# PCB_LED_CALENDAR__ESP-12E.net
KiCad netlist of a schematic drawn in Altium Designer
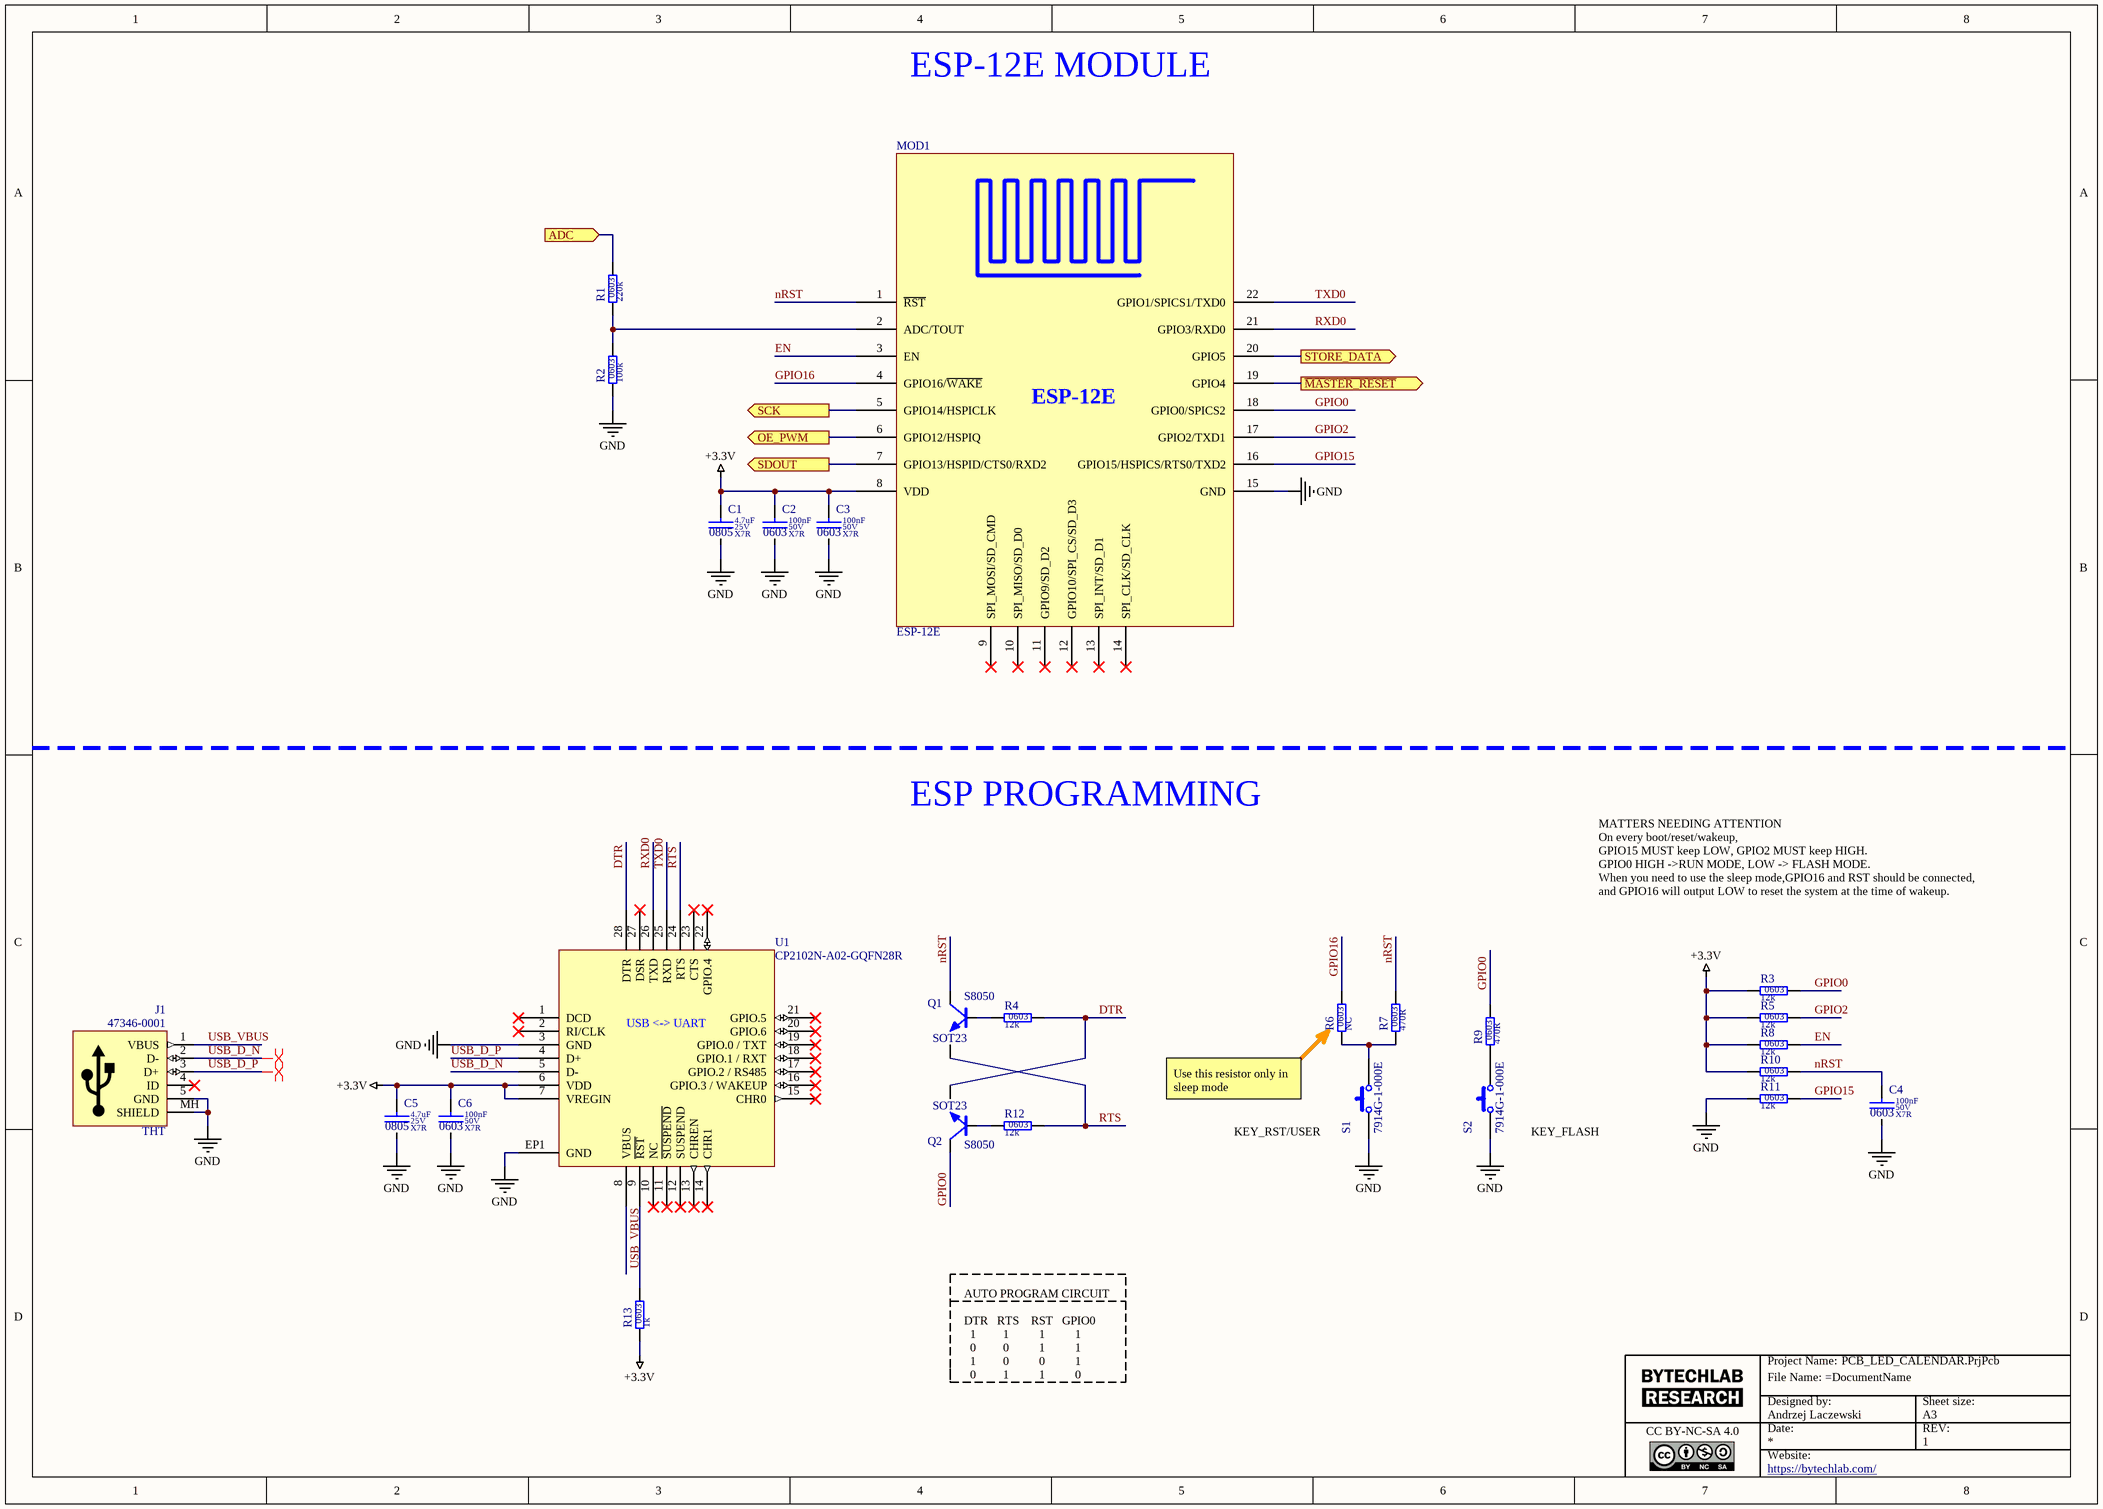
[diagram p0: PCB_LED_CALENDAR__ESP-12E.SchDoc]

(export (version "E")
  (design (tool "Eeschema 10.0.6"))
  (components
    (comp (ref "C1")
      (value "4.7uF")
      (footprint "C_0805_2012")
      (description "Capacitor")
      (fields
        (field (name "DIELECTRIC") "X7R")
        (field (name "VOLTAGE") "25V")
        (field (name "SCH_FOOTPRINT") "0805")
        (field (name "PART NUMBER") "C_4.7uF_25V_X7R_0805_10")
        (field (name "MANUFACTURER") "TDK")
      )
      (libsource (lib "Library") (part "C"))
    )
    (comp (ref "C2")
      (value "100nF")
      (footprint "C_0603_1608")
      (description "Capacitor")
      (fields
        (field (name "DIELECTRIC") "X7R")
        (field (name "VOLTAGE") "50V")
        (field (name "SCH_FOOTPRINT") "0603")
        (field (name "PART NUMBER") "C_100nF_50V_X7R_0603_5")
        (field (name "MANUFACTURER") "Samsung")
      )
      (libsource (lib "Library") (part "C"))
    )
    (comp (ref "C3")
      (value "100nF")
      (footprint "C_0603_1608")
      (description "Capacitor")
      (fields
        (field (name "DIELECTRIC") "X7R")
        (field (name "VOLTAGE") "50V")
        (field (name "SCH_FOOTPRINT") "0603")
        (field (name "PART NUMBER") "C_100nF_50V_X7R_0603_5")
        (field (name "MANUFACTURER") "Samsung")
      )
      (libsource (lib "Library") (part "C"))
    )
    (comp (ref "C4")
      (value "100nF")
      (footprint "C_0603_1608")
      (description "Capacitor")
      (fields
        (field (name "DIELECTRIC") "X7R")
        (field (name "VOLTAGE") "50V")
        (field (name "SCH_FOOTPRINT") "0603")
        (field (name "PART NUMBER") "C_100nF_50V_X7R_0603_5")
        (field (name "MANUFACTURER") "Samsung")
      )
      (libsource (lib "Library") (part "C"))
    )
    (comp (ref "C5")
      (value "4.7uF")
      (footprint "C_0805_2012")
      (description "Capacitor")
      (fields
        (field (name "DIELECTRIC") "X7R")
        (field (name "VOLTAGE") "25V")
        (field (name "SCH_FOOTPRINT") "0805")
        (field (name "PART NUMBER") "C_4.7uF_25V_X7R_0805_10")
        (field (name "MANUFACTURER") "TDK")
      )
      (libsource (lib "Library") (part "C"))
    )
    (comp (ref "C6")
      (value "100nF")
      (footprint "C_0603_1608")
      (description "Capacitor")
      (fields
        (field (name "DIELECTRIC") "X7R")
        (field (name "VOLTAGE") "50V")
        (field (name "SCH_FOOTPRINT") "0603")
        (field (name "PART NUMBER") "C_100nF_50V_X7R_0603_5")
        (field (name "MANUFACTURER") "Samsung")
      )
      (libsource (lib "Library") (part "C"))
    )
    (comp (ref "J1")
      (value "47346-0001")
      (footprint "J_USB_MICROB_47346-0001")
      (description "USB A THT Connector")
      (fields
        (field (name "SCH_FOOTPRINT") "THT")
        (field (name "PART NUMBER") "J_USB_MICROB_47346-0001")
        (field (name "MANUFACTURER") "Molex")
      )
      (libsource (lib "Library") (part "J_USB_2.0_5pin"))
    )
    (comp (ref "MOD1")
      (value "ESP-12E")
      (footprint "ESP-12E")
      (description "ESP-12E Wi-Fi Module by AI-Thinker")
      (fields (field (name "MANUFACTURER") "Ai-thinker"))
      (libsource (lib "PCB_LED_CALENDAR") (part "MOD_ESP_12_E"))
    )
    (comp (ref "Q1")
      (value "S8050")
      (footprint "SOT-23")
      (description "25V 300mW 500mA NPN SOT-23 Bipolar (BJT) ROHS")
      (fields (field (name "MANUFACTURER") "FUXINSEMI") (field (name "SCH_FOOTPRINT") "SOT23"))
      (libsource (lib "PCB_LED_CALENDAR") (part "QNP_S8050"))
    )
    (comp (ref "Q2")
      (value "S8050")
      (footprint "SOT-23")
      (description "25V 300mW 500mA NPN SOT-23 Bipolar (BJT) ROHS")
      (fields (field (name "MANUFACTURER") "FUXINSEMI") (field (name "SCH_FOOTPRINT") "SOT23"))
      (libsource (lib "PCB_LED_CALENDAR") (part "QNP_S8050"))
    )
    (comp (ref "R1")
      (value "220k")
      (footprint "R_0603_1608")
      (fields
        (field (name "SCH_FOOTPRINT") "0603")
        (field (name "PART NUMBER") "R_220k_0603_1")
        (field (name "VOLTAGE") "75V")
        (field (name "POWER") "100mW")
      )
      (libsource (lib "Library") (part "R"))
    )
    (comp (ref "R2")
      (value "100k")
      (footprint "R_0603_1608")
      (fields
        (field (name "SCH_FOOTPRINT") "0603")
        (field (name "PART NUMBER") "R_100k_0603_1")
        (field (name "VOLTAGE") "50V")
        (field (name "POWER") "100mW")
      )
      (libsource (lib "Library") (part "R"))
    )
    (comp (ref "R3")
      (value "12k")
      (footprint "R_0603_1608")
      (fields
        (field (name "SCH_FOOTPRINT") "0603")
        (field (name "PART NUMBER") "R_12k_0603_1")
        (field (name "VOLTAGE") "50V")
        (field (name "POWER") "100mW")
      )
      (libsource (lib "Library") (part "R"))
    )
    (comp (ref "R4")
      (value "12k")
      (footprint "R_0603_1608")
      (fields
        (field (name "SCH_FOOTPRINT") "0603")
        (field (name "PART NUMBER") "R_12k_0603_1")
        (field (name "VOLTAGE") "50V")
        (field (name "POWER") "100mW")
      )
      (libsource (lib "Library") (part "R"))
    )
    (comp (ref "R5")
      (value "12k")
      (footprint "R_0603_1608")
      (fields
        (field (name "SCH_FOOTPRINT") "0603")
        (field (name "PART NUMBER") "R_12k_0603_1")
        (field (name "VOLTAGE") "50V")
        (field (name "POWER") "100mW")
      )
      (libsource (lib "Library") (part "R"))
    )
    (comp (ref "R6")
      (value "NC")
      (footprint "R_NC_0603_1608")
      (fields
        (field (name "SCH_FOOTPRINT") "0603")
        (field (name "PART NUMBER") "R_GENERIC_0603")
        (field (name "Comment") "Resistor")
      )
      (libsource (lib "Library") (part "R"))
    )
    (comp (ref "R7")
      (value "470R")
      (footprint "R_0603_1608")
      (fields
        (field (name "SCH_FOOTPRINT") "0603")
        (field (name "PART NUMBER") "R_470R_0603_1")
        (field (name "VOLTAGE") "50V")
        (field (name "POWER") "100mW")
      )
      (libsource (lib "Library") (part "R"))
    )
    (comp (ref "R8")
      (value "12k")
      (footprint "R_0603_1608")
      (fields
        (field (name "SCH_FOOTPRINT") "0603")
        (field (name "PART NUMBER") "R_12k_0603_1")
        (field (name "VOLTAGE") "50V")
        (field (name "POWER") "100mW")
      )
      (libsource (lib "Library") (part "R"))
    )
    (comp (ref "R9")
      (value "470R")
      (footprint "R_0603_1608")
      (fields
        (field (name "SCH_FOOTPRINT") "0603")
        (field (name "PART NUMBER") "R_470R_0603_1")
        (field (name "VOLTAGE") "50V")
        (field (name "POWER") "100mW")
      )
      (libsource (lib "Library") (part "R"))
    )
    (comp (ref "R10")
      (value "12k")
      (footprint "R_0603_1608")
      (fields
        (field (name "SCH_FOOTPRINT") "0603")
        (field (name "PART NUMBER") "R_12k_0603_1")
        (field (name "VOLTAGE") "50V")
        (field (name "POWER") "100mW")
      )
      (libsource (lib "Library") (part "R"))
    )
    (comp (ref "R11")
      (value "12k")
      (footprint "R_0603_1608")
      (fields
        (field (name "SCH_FOOTPRINT") "0603")
        (field (name "PART NUMBER") "R_12k_0603_1")
        (field (name "VOLTAGE") "50V")
        (field (name "POWER") "100mW")
      )
      (libsource (lib "Library") (part "R"))
    )
    (comp (ref "R12")
      (value "12k")
      (footprint "R_0603_1608")
      (fields
        (field (name "SCH_FOOTPRINT") "0603")
        (field (name "PART NUMBER") "R_12k_0603_1")
        (field (name "VOLTAGE") "50V")
        (field (name "POWER") "100mW")
      )
      (libsource (lib "Library") (part "R"))
    )
    (comp (ref "R13")
      (value "1k")
      (footprint "R_0603_1608")
      (fields
        (field (name "SCH_FOOTPRINT") "0603")
        (field (name "PART NUMBER") "R_1k_0603_1")
        (field (name "VOLTAGE") "75V")
        (field (name "POWER") "100mW")
      )
      (libsource (lib "Library") (part "R"))
    )
    (comp (ref "S1")
      (value "7914G-1-000E")
      (footprint "7914G-1-000E")
      (description "Tact Switch")
      (fields (field (name "MANUFACTURER") "BOURNS"))
      (libsource (lib "PCB_LED_CALENDAR") (part "S_7914G-1-000E"))
    )
    (comp (ref "S2")
      (value "7914G-1-000E")
      (footprint "7914G-1-000E")
      (description "Tact Switch")
      (fields (field (name "MANUFACTURER") "BOURNS"))
      (libsource (lib "PCB_LED_CALENDAR") (part "S_7914G-1-000E"))
    )
    (comp (ref "U1")
      (value "CP2102N-A02-GQFN28R")
      (footprint "QFN28")
      (description "USB to UART UART QFN-28-EP(5x5) USB Converters ROHS")
      (fields (field (name "MANUFACTURER") "SKYWORKS/SILICON LABS"))
      (libsource (lib "PCB_LED_CALENDAR") (part "U_CP2102N-A02-GQFN28R"))
    )
  )
  (nets
    (net (code "1") (name "+3.3V") (class "Default")
      (node (ref "C1") (pin "1") (pinfunction "1_1") (pintype "passive"))
      (node (ref "C2") (pin "1") (pinfunction "1_1") (pintype "passive"))
      (node (ref "C3") (pin "1") (pinfunction "1_1") (pintype "passive"))
      (node (ref "C5") (pin "1") (pinfunction "1_1") (pintype "passive"))
      (node (ref "C6") (pin "1") (pinfunction "1_1") (pintype "passive"))
      (node (ref "MOD1") (pin "8") (pinfunction "VDD_8") (pintype "passive"))
      (node (ref "R10") (pin "1") (pinfunction "1_1") (pintype "passive"))
      (node (ref "R13") (pin "1") (pinfunction "1_1") (pintype "passive"))
      (node (ref "R3") (pin "1") (pinfunction "1_1") (pintype "passive"))
      (node (ref "R5") (pin "1") (pinfunction "1_1") (pintype "passive"))
      (node (ref "R8") (pin "1") (pinfunction "1_1") (pintype "passive"))
      (node (ref "U1") (pin "6") (pinfunction "VDD_6") (pintype "passive"))
      (node (ref "U1") (pin "7") (pinfunction "VREGIN_7") (pintype "passive"))
    )
    (net (code "2") (name "/ADC") (class "Default")
      (node (ref "R1") (pin "2") (pinfunction "2_2") (pintype "passive"))
    )
    (net (code "3") (name "/DTR") (class "Default")
      (node (ref "Q2") (pin "E") (pinfunction "E_E") (pintype "passive"))
      (node (ref "R4") (pin "2") (pinfunction "2_2") (pintype "passive"))
      (node (ref "U1") (pin "28") (pinfunction "DTR_28") (pintype "passive"))
    )
    (net (code "4") (name "/EN") (class "Default")
      (node (ref "MOD1") (pin "3") (pinfunction "EN_3") (pintype "passive"))
      (node (ref "R8") (pin "2") (pinfunction "2_2") (pintype "passive"))
    )
    (net (code "5") (name "/GPIO0") (class "Default")
      (node (ref "MOD1") (pin "18") (pinfunction "GPIO0/SPICS2_18") (pintype "passive"))
      (node (ref "Q2") (pin "C") (pinfunction "C_C") (pintype "passive"))
      (node (ref "R3") (pin "2") (pinfunction "2_2") (pintype "passive"))
      (node (ref "R9") (pin "2") (pinfunction "2_2") (pintype "passive"))
    )
    (net (code "6") (name "/GPIO2") (class "Default")
      (node (ref "MOD1") (pin "17") (pinfunction "GPIO2/TXD1_17") (pintype "passive"))
      (node (ref "R5") (pin "2") (pinfunction "2_2") (pintype "passive"))
    )
    (net (code "7") (name "/GPIO15") (class "Default")
      (node (ref "MOD1") (pin "16") (pinfunction "GPIO15/HSPICS/RTS0/TXD2_16") (pintype "passive"))
      (node (ref "R11") (pin "2") (pinfunction "2_2") (pintype "passive"))
    )
    (net (code "8") (name "/GPIO16") (class "Default")
      (node (ref "MOD1") (pin "4") (pinfunction "GPIO16/~{WAKE}_4") (pintype "passive"))
      (node (ref "R6") (pin "2") (pinfunction "2_2") (pintype "passive"))
    )
    (net (code "9") (name "/OE_PWM") (class "Default")
      (node (ref "MOD1") (pin "6") (pinfunction "GPIO12/HSPIQ_6") (pintype "passive"))
    )
    (net (code "10") (name "/RTS") (class "Default")
      (node (ref "Q1") (pin "E") (pinfunction "E_E") (pintype "passive"))
      (node (ref "R12") (pin "2") (pinfunction "2_2") (pintype "passive"))
      (node (ref "U1") (pin "24") (pinfunction "RTS_24") (pintype "passive"))
    )
    (net (code "11") (name "/RXD0") (class "Default")
      (node (ref "MOD1") (pin "21") (pinfunction "GPIO3/RXD0_21") (pintype "passive"))
      (node (ref "U1") (pin "26") (pinfunction "TXD_26") (pintype "passive"))
    )
    (net (code "12") (name "/SCK") (class "Default")
      (node (ref "MOD1") (pin "5") (pinfunction "GPIO14/HSPICLK_5") (pintype "passive"))
    )
    (net (code "13") (name "/SDOUT") (class "Default")
      (node (ref "MOD1") (pin "7") (pinfunction "GPIO13/HSPID/CTS0/RXD2_7") (pintype "passive"))
    )
    (net (code "14") (name "/STORE_DATA") (class "Default")
      (node (ref "MOD1") (pin "20") (pinfunction "GPIO5_20") (pintype "passive"))
    )
    (net (code "15") (name "/TXD0") (class "Default")
      (node (ref "MOD1") (pin "22") (pinfunction "GPIO1/SPICS1/TXD0_22") (pintype "passive"))
      (node (ref "U1") (pin "25") (pinfunction "RXD_25") (pintype "passive"))
    )
    (net (code "16") (name "/USB_D_N") (class "Default")
      (node (ref "J1") (pin "2") (pinfunction "D-_2") (pintype "bidirectional"))
      (node (ref "U1") (pin "5") (pinfunction "D-_5") (pintype "passive"))
    )
    (net (code "17") (name "/USB_D_P") (class "Default")
      (node (ref "J1") (pin "3") (pinfunction "D+_3") (pintype "bidirectional"))
      (node (ref "U1") (pin "4") (pinfunction "D+_4") (pintype "passive"))
    )
    (net (code "18") (name "/USB_VBUS") (class "Default")
      (node (ref "J1") (pin "1") (pinfunction "VBUS_1") (pintype "output"))
      (node (ref "U1") (pin "8") (pinfunction "VBUS_8") (pintype "passive"))
    )
    (net (code "19") (name "/nRST") (class "Default")
      (node (ref "C4") (pin "1") (pinfunction "1_1") (pintype "passive"))
      (node (ref "MOD1") (pin "1") (pinfunction "~{RST}_1") (pintype "passive"))
      (node (ref "Q1") (pin "C") (pinfunction "C_C") (pintype "passive"))
      (node (ref "R10") (pin "2") (pinfunction "2_2") (pintype "passive"))
      (node (ref "R7") (pin "2") (pinfunction "2_2") (pintype "passive"))
    )
    (net (code "20") (name "/~{MASTER_RESET}") (class "Default")
      (node (ref "MOD1") (pin "19") (pinfunction "GPIO4_19") (pintype "passive"))
    )
    (net (code "21") (name "GND") (class "Default")
      (node (ref "C1") (pin "2") (pinfunction "2_2") (pintype "passive"))
      (node (ref "C2") (pin "2") (pinfunction "2_2") (pintype "passive"))
      (node (ref "C3") (pin "2") (pinfunction "2_2") (pintype "passive"))
      (node (ref "C4") (pin "2") (pinfunction "2_2") (pintype "passive"))
      (node (ref "C5") (pin "2") (pinfunction "2_2") (pintype "passive"))
      (node (ref "C6") (pin "2") (pinfunction "2_2") (pintype "passive"))
      (node (ref "J1") (pin "5") (pinfunction "GND_5") (pintype "power_in"))
      (node (ref "J1") (pin "MH") (pinfunction "SHIELD_MH") (pintype "passive"))
      (node (ref "MOD1") (pin "15") (pinfunction "GND_15") (pintype "passive"))
      (node (ref "R11") (pin "1") (pinfunction "1_1") (pintype "passive"))
      (node (ref "R2") (pin "1") (pinfunction "1_1") (pintype "passive"))
      (node (ref "S1") (pin "1") (pinfunction "1_1") (pintype "passive"))
      (node (ref "S2") (pin "1") (pinfunction "1_1") (pintype "passive"))
      (node (ref "U1") (pin "3") (pinfunction "GND_3") (pintype "passive"))
      (node (ref "U1") (pin "EP1") (pinfunction "GND_EP1") (pintype "passive"))
    )
    (net (code "22") (name "Net-(MOD1-ADC{slash}TOUT)") (class "Default")
      (node (ref "MOD1") (pin "2") (pinfunction "ADC/TOUT_2") (pintype "passive"))
      (node (ref "R1") (pin "1") (pinfunction "1_1") (pintype "passive"))
      (node (ref "R2") (pin "2") (pinfunction "2_2") (pintype "passive"))
    )
    (net (code "23") (name "Net-(Q1-PadB)") (class "Default")
      (node (ref "Q1") (pin "B") (pinfunction "B_B") (pintype "passive"))
      (node (ref "R4") (pin "1") (pinfunction "1_1") (pintype "passive"))
    )
    (net (code "24") (name "Net-(Q2-PadB)") (class "Default")
      (node (ref "Q2") (pin "B") (pinfunction "B_B") (pintype "passive"))
      (node (ref "R12") (pin "1") (pinfunction "1_1") (pintype "passive"))
    )
    (net (code "25") (name "Net-(R6-Pad1)") (class "Default")
      (node (ref "R6") (pin "1") (pinfunction "1_1") (pintype "passive"))
      (node (ref "R7") (pin "1") (pinfunction "1_1") (pintype "passive"))
      (node (ref "S1") (pin "2") (pinfunction "2_2") (pintype "passive"))
    )
    (net (code "26") (name "Net-(R9-Pad1)") (class "Default")
      (node (ref "R9") (pin "1") (pinfunction "1_1") (pintype "passive"))
      (node (ref "S2") (pin "2") (pinfunction "2_2") (pintype "passive"))
    )
    (net (code "27") (name "Net-(U1-~{RST})") (class "Default")
      (node (ref "R13") (pin "2") (pinfunction "2_2") (pintype "passive"))
      (node (ref "U1") (pin "9") (pinfunction "~{RST}_9") (pintype "passive"))
    )
    (net (code "28") (name "unconnected-(J1-ID-Pad4)") (class "Default")
      (node (ref "J1") (pin "4") (pinfunction "ID_4") (pintype "power_in+no_connect"))
    )
    (net (code "29") (name "unconnected-(MOD1-GPIO9{slash}SD_D2-Pad11)") (class "Default")
      (node (ref "MOD1") (pin "11") (pinfunction "GPIO9/SD_D2_11") (pintype "passive+no_connect"))
    )
    (net (code "30") (name "unconnected-(MOD1-GPIO10{slash}SPI_CS{slash}SD_D3-Pad12)") (class "Default")
      (node (ref "MOD1") (pin "12") (pinfunction "GPIO10/SPI_CS/SD_D3_12") (pintype "passive+no_connect"))
    )
    (net (code "31") (name "unconnected-(MOD1-SPI_CLK{slash}SD_CLK-Pad14)") (class "Default")
      (node (ref "MOD1") (pin "14") (pinfunction "SPI_CLK/SD_CLK_14") (pintype "passive+no_connect"))
    )
    (net (code "32") (name "unconnected-(MOD1-SPI_INT{slash}SD_D1-Pad13)") (class "Default")
      (node (ref "MOD1") (pin "13") (pinfunction "SPI_INT/SD_D1_13") (pintype "passive+no_connect"))
    )
    (net (code "33") (name "unconnected-(MOD1-SPI_MISO{slash}SD_D0-Pad10)") (class "Default")
      (node (ref "MOD1") (pin "10") (pinfunction "SPI_MISO/SD_D0_10") (pintype "passive+no_connect"))
    )
    (net (code "34") (name "unconnected-(MOD1-SPI_MOSI{slash}SD_CMD-Pad9)") (class "Default")
      (node (ref "MOD1") (pin "9") (pinfunction "SPI_MOSI/SD_CMD_9") (pintype "passive+no_connect"))
    )
    (net (code "35") (name "unconnected-(U1-CHR0-Pad15)") (class "Default")
      (node (ref "U1") (pin "15") (pinfunction "CHR0_15") (pintype "output+no_connect"))
    )
    (net (code "36") (name "unconnected-(U1-CHR1-Pad14)") (class "Default")
      (node (ref "U1") (pin "14") (pinfunction "CHR1_14") (pintype "output+no_connect"))
    )
    (net (code "37") (name "unconnected-(U1-CHREN-Pad13)") (class "Default")
      (node (ref "U1") (pin "13") (pinfunction "CHREN_13") (pintype "output+no_connect"))
    )
    (net (code "38") (name "unconnected-(U1-CTS-Pad23)") (class "Default")
      (node (ref "U1") (pin "23") (pinfunction "CTS_23") (pintype "passive+no_connect"))
    )
    (net (code "39") (name "unconnected-(U1-DCD-Pad1)") (class "Default")
      (node (ref "U1") (pin "1") (pinfunction "DCD_1") (pintype "passive+no_connect"))
    )
    (net (code "40") (name "unconnected-(U1-DSR-Pad27)") (class "Default")
      (node (ref "U1") (pin "27") (pinfunction "DSR_27") (pintype "passive+no_connect"))
    )
    (net (code "41") (name "unconnected-(U1-GPIO.0_{slash}_TXT-Pad19)") (class "Default")
      (node (ref "U1") (pin "19") (pinfunction "GPIO.0_/_TXT_19") (pintype "bidirectional+no_connect"))
    )
    (net (code "42") (name "unconnected-(U1-GPIO.1_{slash}_RXT-Pad18)") (class "Default")
      (node (ref "U1") (pin "18") (pinfunction "GPIO.1_/_RXT_18") (pintype "bidirectional+no_connect"))
    )
    (net (code "43") (name "unconnected-(U1-GPIO.2_{slash}_RS485-Pad17)") (class "Default")
      (node (ref "U1") (pin "17") (pinfunction "GPIO.2_/_RS485_17") (pintype "bidirectional+no_connect"))
    )
    (net (code "44") (name "unconnected-(U1-GPIO.3_{slash}_WAKEUP-Pad16)") (class "Default")
      (node (ref "U1") (pin "16") (pinfunction "GPIO.3_/_WAKEUP_16") (pintype "bidirectional+no_connect"))
    )
    (net (code "45") (name "unconnected-(U1-GPIO.4-Pad22)") (class "Default")
      (node (ref "U1") (pin "22") (pinfunction "GPIO.4_22") (pintype "bidirectional+no_connect"))
    )
    (net (code "46") (name "unconnected-(U1-GPIO.5-Pad21)") (class "Default")
      (node (ref "U1") (pin "21") (pinfunction "GPIO.5_21") (pintype "bidirectional+no_connect"))
    )
    (net (code "47") (name "unconnected-(U1-GPIO.6-Pad20)") (class "Default")
      (node (ref "U1") (pin "20") (pinfunction "GPIO.6_20") (pintype "bidirectional+no_connect"))
    )
    (net (code "48") (name "unconnected-(U1-NC-Pad10)") (class "Default")
      (node (ref "U1") (pin "10") (pinfunction "NC_10") (pintype "passive+no_connect"))
    )
    (net (code "49") (name "unconnected-(U1-RI{slash}CLK-Pad2)") (class "Default")
      (node (ref "U1") (pin "2") (pinfunction "RI/CLK_2") (pintype "passive+no_connect"))
    )
    (net (code "50") (name "unconnected-(U1-SUSPEND-Pad12)") (class "Default")
      (node (ref "U1") (pin "12") (pinfunction "SUSPEND_12") (pintype "passive+no_connect"))
    )
    (net (code "51") (name "unconnected-(U1-~{SUSPEND}-Pad11)") (class "Default")
      (node (ref "U1") (pin "11") (pinfunction "~{SUSPEND}_11") (pintype "passive+no_connect"))
    )
  )
)
